# ns2012.net
KiCad netlist of a schematic drawn in EAGLE
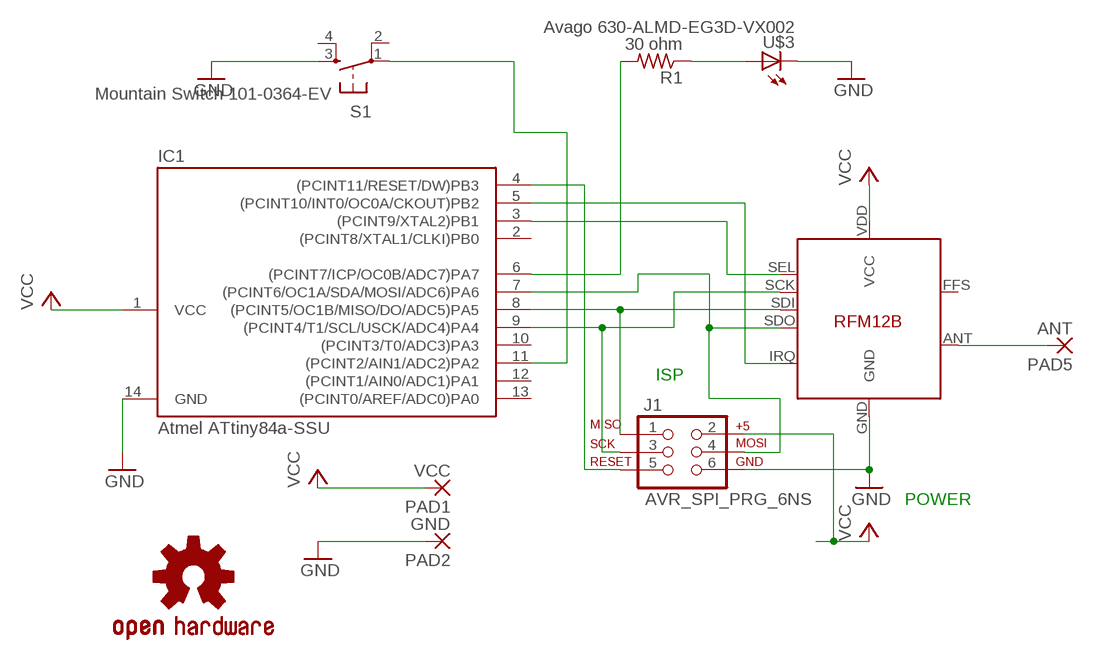
[diagram p0: schematic, sheet 1]

(export (version "E")
  (design (tool "Eeschema 10.0.6"))
  (components
    (comp (ref "IC1")
      (value "Atmel ATtiny84a-SSU")
      (footprint "eagle-import:SOIC14")
      (libsource (lib "eagle-import") (part "TINY24/44/84-SSU"))
    )
    (comp (ref "J1")
      (value "AVR_SPI_PRG_6NS")
      (footprint "eagle-import:2X3-NS")
      (libsource (lib "eagle-import") (part "AVR_SPI_PRG_6NS"))
    )
    (comp (ref "PAD1")
      (value "VCC")
      (footprint "eagle-import:2,15_1,0")
      (libsource (lib "eagle-import") (part "2,15/1,0"))
    )
    (comp (ref "PAD2")
      (value "GND")
      (footprint "eagle-import:2,15_1,0")
      (libsource (lib "eagle-import") (part "2,15/1,0"))
    )
    (comp (ref "PAD5")
      (value "ANT")
      (footprint "eagle-import:2,15_1,0")
      (libsource (lib "eagle-import") (part "2,15/1,0"))
    )
    (comp (ref "R1")
      (value "30 ohm")
      (footprint "eagle-import:R0805")
      (libsource (lib "eagle-import") (part "R-US_R0805"))
    )
    (comp (ref "RFM12B")
      (value "HopeRF RFM12B-433S1")
      (footprint "eagle-import:RFM12B-NARROW")
      (libsource (lib "eagle-import") (part "RFM12BN"))
    )
    (comp (ref "S1")
      (value "Mountain Switch 101-0364-EV")
      (footprint "eagle-import:DTSM-6")
      (libsource (lib "eagle-import") (part "DTSM-6"))
    )
    (comp (ref "U$1")
      (value "OSHW-LOGOS")
      (footprint "eagle-import:OSHW-LOGO-S")
      (libsource (lib "eagle-import") (part "OSHW-LOGOS"))
    )
    (comp (ref "U$3")
      (value "Avago 630-ALMD-EG3D-VX002")
      (footprint "eagle-import:ALMD-__3D")
      (libsource (lib "eagle-import") (part "ALMD-XX3D"))
    )
  )
  (nets
    (net (code "1") (name "GND") (class "Default")
      (node (ref "IC1") (pin "14") (pinfunction "GND_14") (pintype "power_in"))
      (node (ref "J1") (pin "6") (pinfunction "6_6") (pintype "passive"))
      (node (ref "PAD2") (pin "1") (pinfunction "P_1") (pintype "passive"))
      (node (ref "RFM12B") (pin "GND") (pinfunction "GND_GND") (pintype "power_in"))
      (node (ref "S1") (pin "3") (pinfunction "3_3") (pintype "passive"))
      (node (ref "U$3") (pin "C1") (pinfunction "C_C1") (pintype "passive"))
      (node (ref "U$3") (pin "C2") (pinfunction "C_C2") (pintype "passive"))
    )
    (net (code "2") (name "Net-(IC1-(PCINT2{slash}AIN1{slash}ADC2)PA2)") (class "Default")
      (node (ref "IC1") (pin "11") (pinfunction "(PCINT2/AIN1/ADC2)PA2_11") (pintype "bidirectional"))
      (node (ref "S1") (pin "1") (pinfunction "1_1") (pintype "passive"))
    )
    (net (code "3") (name "Net-(IC1-(PCINT4{slash}T1{slash}SCL{slash}USCK{slash}ADC4)PA4)") (class "Default")
      (node (ref "IC1") (pin "9") (pinfunction "(PCINT4/T1/SCL/USCK/ADC4)PA4_9") (pintype "bidirectional"))
      (node (ref "J1") (pin "3") (pinfunction "3_3") (pintype "passive"))
      (node (ref "RFM12B") (pin "SCK") (pinfunction "SCK_SCK") (pintype "input"))
    )
    (net (code "4") (name "Net-(IC1-(PCINT5{slash}OC1B{slash}MISO{slash}DO{slash}ADC5)PA5)") (class "Default")
      (node (ref "IC1") (pin "8") (pinfunction "(PCINT5/OC1B/MISO/DO/ADC5)PA5_8") (pintype "bidirectional"))
      (node (ref "J1") (pin "1") (pinfunction "1_1") (pintype "passive"))
      (node (ref "RFM12B") (pin "SDI") (pinfunction "SDI_SDI") (pintype "input"))
    )
    (net (code "5") (name "Net-(IC1-(PCINT6{slash}OC1A{slash}SDA{slash}MOSI{slash}ADC6)PA6)") (class "Default")
      (node (ref "IC1") (pin "7") (pinfunction "(PCINT6/OC1A/SDA/MOSI/ADC6)PA6_7") (pintype "bidirectional"))
      (node (ref "J1") (pin "4") (pinfunction "4_4") (pintype "passive"))
      (node (ref "RFM12B") (pin "SDO") (pinfunction "SDO_SDO") (pintype "output"))
    )
    (net (code "6") (name "Net-(IC1-(PCINT7{slash}ICP{slash}OC0B{slash}ADC7)PA7)") (class "Default")
      (node (ref "IC1") (pin "6") (pinfunction "(PCINT7/ICP/OC0B/ADC7)PA7_6") (pintype "bidirectional"))
      (node (ref "R1") (pin "2") (pinfunction "2_2") (pintype "passive"))
    )
    (net (code "7") (name "Net-(IC1-(PCINT9{slash}XTAL2)PB1)") (class "Default")
      (node (ref "IC1") (pin "3") (pinfunction "(PCINT9/XTAL2)PB1_3") (pintype "bidirectional"))
      (node (ref "RFM12B") (pin "SEL") (pinfunction "SEL_SEL") (pintype "input"))
    )
    (net (code "8") (name "Net-(IC1-(PCINT10{slash}INT0{slash}OC0A{slash}CKOUT)PB2)") (class "Default")
      (node (ref "IC1") (pin "5") (pinfunction "(PCINT10/INT0/OC0A/CKOUT)PB2_5") (pintype "bidirectional"))
      (node (ref "RFM12B") (pin "IRQ") (pinfunction "IRQ_IRQ") (pintype "open_collector"))
    )
    (net (code "9") (name "Net-(IC1-(PCINT11{slash}RESET{slash}DW)PB3)") (class "Default")
      (node (ref "IC1") (pin "4") (pinfunction "(PCINT11/RESET/DW)PB3_4") (pintype "bidirectional"))
      (node (ref "J1") (pin "5") (pinfunction "5_5") (pintype "passive"))
    )
    (net (code "10") (name "Net-(PAD5-P)") (class "Default")
      (node (ref "PAD5") (pin "1") (pinfunction "P_1") (pintype "passive"))
      (node (ref "RFM12B") (pin "ANT") (pinfunction "ANT_ANT") (pintype "passive"))
    )
    (net (code "11") (name "Net-(R1-Pad1)") (class "Default")
      (node (ref "R1") (pin "1") (pinfunction "1_1") (pintype "passive"))
      (node (ref "U$3") (pin "A1") (pinfunction "A_A1") (pintype "passive"))
      (node (ref "U$3") (pin "A2") (pinfunction "A_A2") (pintype "passive"))
    )
    (net (code "12") (name "VCC") (class "Default")
      (node (ref "IC1") (pin "1") (pinfunction "VCC_1") (pintype "power_in"))
      (node (ref "J1") (pin "2") (pinfunction "2_2") (pintype "passive"))
      (node (ref "PAD1") (pin "1") (pinfunction "P_1") (pintype "passive"))
      (node (ref "RFM12B") (pin "VDD") (pinfunction "VCC_VDD") (pintype "power_in"))
    )
    (net (code "13") (name "unconnected-(IC1-(PCINT0{slash}AREF{slash}ADC0)PA0-Pad13)") (class "Default")
      (node (ref "IC1") (pin "13") (pinfunction "(PCINT0/AREF/ADC0)PA0_13") (pintype "bidirectional"))
    )
    (net (code "14") (name "unconnected-(IC1-(PCINT1{slash}AIN0{slash}ADC1)PA1-Pad12)") (class "Default")
      (node (ref "IC1") (pin "12") (pinfunction "(PCINT1/AIN0/ADC1)PA1_12") (pintype "bidirectional"))
    )
    (net (code "15") (name "unconnected-(IC1-(PCINT3{slash}T0{slash}ADC3)PA3-Pad10)") (class "Default")
      (node (ref "IC1") (pin "10") (pinfunction "(PCINT3/T0/ADC3)PA3_10") (pintype "bidirectional"))
    )
    (net (code "16") (name "unconnected-(IC1-(PCINT8{slash}XTAL1{slash}CLKI)PB0-Pad2)") (class "Default")
      (node (ref "IC1") (pin "2") (pinfunction "(PCINT8/XTAL1/CLKI)PB0_2") (pintype "bidirectional"))
    )
    (net (code "17") (name "unconnected-(RFM12B-PadFFS)") (class "Default")
      (node (ref "RFM12B") (pin "FFS") (pinfunction "FFS_FFS") (pintype "bidirectional"))
    )
    (net (code "18") (name "unconnected-(S1-Pad2)") (class "Default")
      (node (ref "S1") (pin "2") (pinfunction "2_2") (pintype "passive"))
    )
    (net (code "19") (name "unconnected-(S1-Pad4)") (class "Default")
      (node (ref "S1") (pin "4") (pinfunction "4_4") (pintype "passive"))
    )
  )
)
